# design.net
KiCad netlist of a schematic drawn in Altium Designer
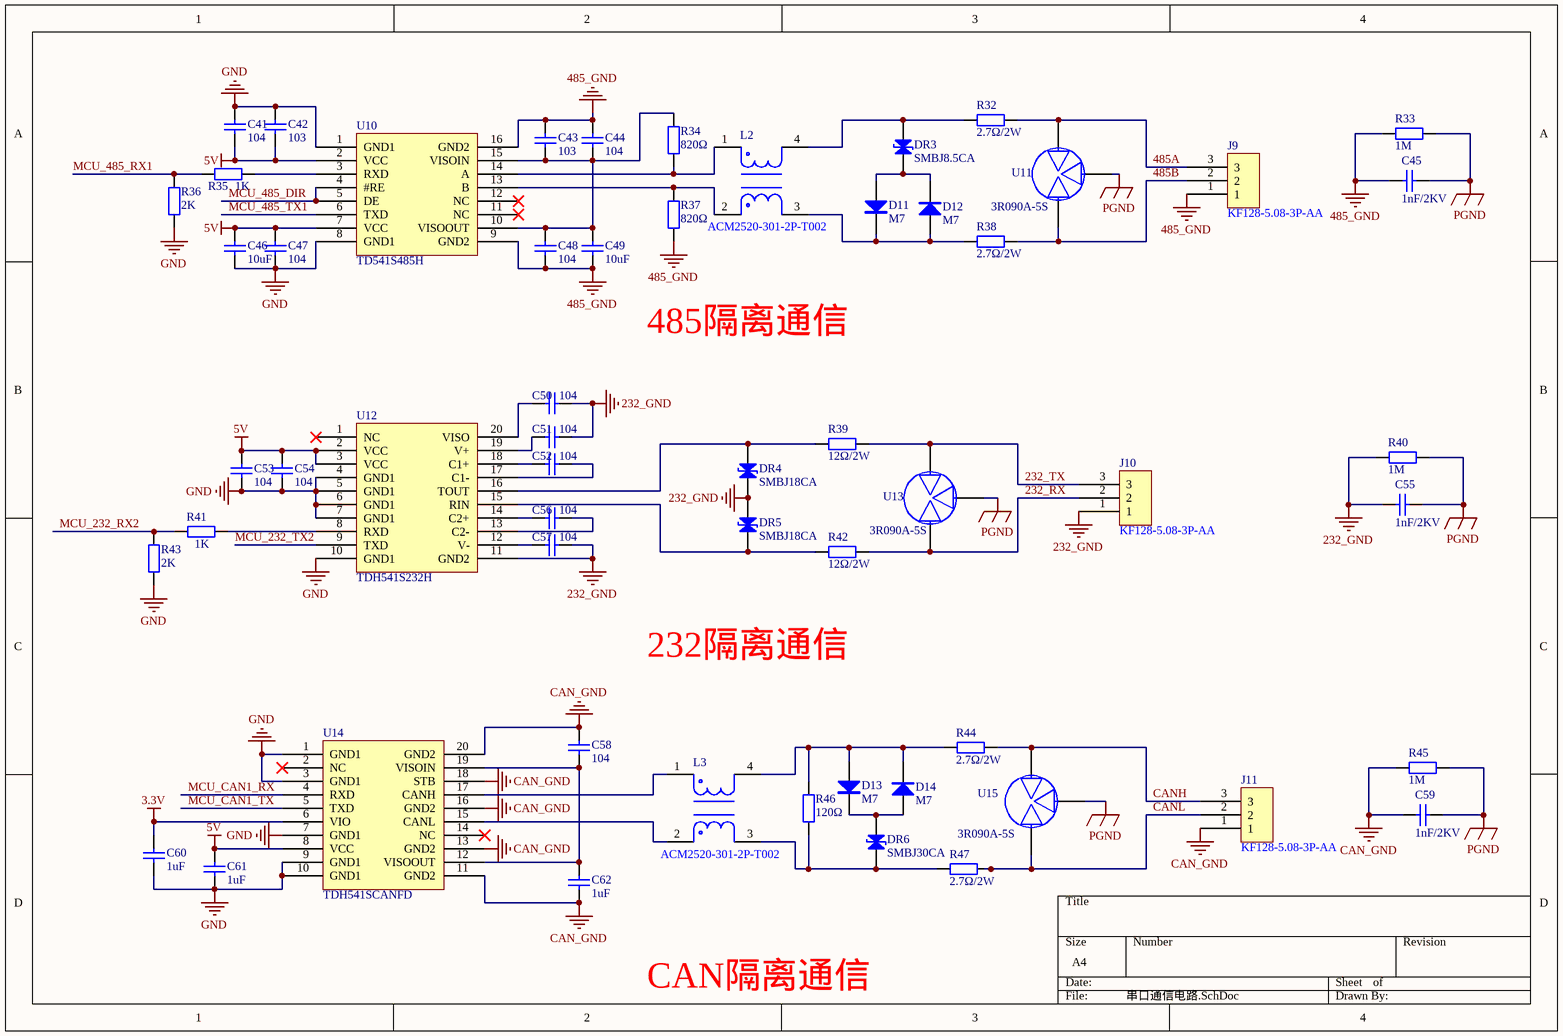
[diagram p0: 串口通信电路.SchDoc]

(export (version "E")
  (design (tool "Eeschema 10.0.6"))
  (components
    (comp (ref "C41")
      (value "104")
      (footprint "C 0603_L")
      (description "0603贴片电容")
      (fields (field (name "PUBLISHER") "Altium Limited"))
      (libsource (lib "STM32_PLC_20251215") (part "Cap"))
    )
    (comp (ref "C42")
      (value "103")
      (footprint "C 0603_L")
      (description "0603贴片电容")
      (fields (field (name "PUBLISHER") "Altium Limited"))
      (libsource (lib "STM32_PLC_20251215") (part "Cap"))
    )
    (comp (ref "C43")
      (value "103")
      (footprint "C 0603_L")
      (description "0603贴片电容")
      (fields (field (name "PUBLISHER") "Altium Limited"))
      (libsource (lib "STM32_PLC_20251215") (part "Cap"))
    )
    (comp (ref "C44")
      (value "104")
      (footprint "C 0603_L")
      (description "0603贴片电容")
      (fields (field (name "PUBLISHER") "Altium Limited"))
      (libsource (lib "STM32_PLC_20251215") (part "Cap"))
    )
    (comp (ref "C45")
      (value "1nF/2KV")
      (footprint "C1206_L")
      (description "0603贴片电容")
      (fields (field (name "PUBLISHER") "Altium Limited"))
      (libsource (lib "STM32_PLC_20251215") (part "Cap"))
    )
    (comp (ref "C46")
      (value "10uF")
      (footprint "C 0603_L")
      (description "0603贴片电容")
      (fields (field (name "PUBLISHER") "Altium Limited"))
      (libsource (lib "STM32_PLC_20251215") (part "Cap"))
    )
    (comp (ref "C47")
      (value "104")
      (footprint "C 0603_L")
      (description "0603贴片电容")
      (fields (field (name "PUBLISHER") "Altium Limited"))
      (libsource (lib "STM32_PLC_20251215") (part "Cap"))
    )
    (comp (ref "C48")
      (value "104")
      (footprint "C 0603_L")
      (description "0603贴片电容")
      (fields (field (name "PUBLISHER") "Altium Limited"))
      (libsource (lib "STM32_PLC_20251215") (part "Cap"))
    )
    (comp (ref "C49")
      (value "10uF")
      (footprint "C 0603_L")
      (description "0603贴片电容")
      (fields (field (name "PUBLISHER") "Altium Limited"))
      (libsource (lib "STM32_PLC_20251215") (part "Cap"))
    )
    (comp (ref "C50")
      (value "104")
      (footprint "C 0603_L")
      (description "0603贴片电容")
      (fields (field (name "PUBLISHER") "Altium Limited"))
      (libsource (lib "STM32_PLC_20251215") (part "Cap"))
    )
    (comp (ref "C51")
      (value "104")
      (footprint "C 0603_L")
      (description "0603贴片电容")
      (fields (field (name "PUBLISHER") "Altium Limited"))
      (libsource (lib "STM32_PLC_20251215") (part "Cap"))
    )
    (comp (ref "C52")
      (value "104")
      (footprint "C 0603_L")
      (description "0603贴片电容")
      (fields (field (name "PUBLISHER") "Altium Limited"))
      (libsource (lib "STM32_PLC_20251215") (part "Cap"))
    )
    (comp (ref "C53")
      (value "104")
      (footprint "C 0603_L")
      (description "0603贴片电容")
      (fields (field (name "PUBLISHER") "Altium Limited"))
      (libsource (lib "STM32_PLC_20251215") (part "Cap"))
    )
    (comp (ref "C54")
      (value "104")
      (footprint "C 0603_L")
      (description "0603贴片电容")
      (fields (field (name "PUBLISHER") "Altium Limited"))
      (libsource (lib "STM32_PLC_20251215") (part "Cap"))
    )
    (comp (ref "C55")
      (value "1nF/2KV")
      (footprint "C1206_L")
      (description "0603贴片电容")
      (fields (field (name "PUBLISHER") "Altium Limited"))
      (libsource (lib "STM32_PLC_20251215") (part "Cap"))
    )
    (comp (ref "C56")
      (value "104")
      (footprint "C 0603_L")
      (description "0603贴片电容")
      (fields (field (name "PUBLISHER") "Altium Limited"))
      (libsource (lib "STM32_PLC_20251215") (part "Cap"))
    )
    (comp (ref "C57")
      (value "104")
      (footprint "C 0603_L")
      (description "0603贴片电容")
      (fields (field (name "PUBLISHER") "Altium Limited"))
      (libsource (lib "STM32_PLC_20251215") (part "Cap"))
    )
    (comp (ref "C58")
      (value "104")
      (footprint "C 0603_L")
      (description "0603贴片电容")
      (fields (field (name "PUBLISHER") "Altium Limited"))
      (libsource (lib "STM32_PLC_20251215") (part "Cap"))
    )
    (comp (ref "C59")
      (value "1nF/2KV")
      (footprint "C1206_L")
      (description "0603贴片电容")
      (fields (field (name "PUBLISHER") "Altium Limited"))
      (libsource (lib "STM32_PLC_20251215") (part "Cap"))
    )
    (comp (ref "C60")
      (value "1uF")
      (footprint "C 0603_L")
      (description "0603贴片电容")
      (fields (field (name "PUBLISHER") "Altium Limited"))
      (libsource (lib "STM32_PLC_20251215") (part "Cap"))
    )
    (comp (ref "C61")
      (value "1uF")
      (footprint "C 0603_L")
      (description "0603贴片电容")
      (fields (field (name "PUBLISHER") "Altium Limited"))
      (libsource (lib "STM32_PLC_20251215") (part "Cap"))
    )
    (comp (ref "C62")
      (value "1uF")
      (footprint "C 0603_L")
      (description "0603贴片电容")
      (fields (field (name "PUBLISHER") "Altium Limited"))
      (libsource (lib "STM32_PLC_20251215") (part "Cap"))
    )
    (comp (ref "D11")
      (value "M7")
      (footprint "SMA")
      (description "整流二极管")
      (libsource (lib "STM32_PLC_20251215_1") (part "M7"))
    )
    (comp (ref "D12")
      (value "M7")
      (footprint "SMA")
      (description "整流二极管")
      (libsource (lib "STM32_PLC_20251215_1") (part "M7"))
    )
    (comp (ref "D13")
      (value "M7")
      (footprint "SMA")
      (description "整流二极管")
      (libsource (lib "STM32_PLC_20251215_1") (part "M7"))
    )
    (comp (ref "D14")
      (value "M7")
      (footprint "SMA")
      (description "整流二极管")
      (libsource (lib "STM32_PLC_20251215_1") (part "M7"))
    )
    (comp (ref "DR3")
      (value "SMBJ8.5CA")
      (footprint "SMB")
      (description "SMB,瞬态抑制二极管")
      (fields (field (name "版权归属") "源创客"))
      (libsource (lib "STM32_PLC_20251215") (part "TVS"))
    )
    (comp (ref "DR4")
      (value "SMBJ18CA")
      (footprint "SMB")
      (description "SMB,瞬态抑制二极管")
      (fields (field (name "版权归属") "源创客"))
      (libsource (lib "STM32_PLC_20251215") (part "TVS"))
    )
    (comp (ref "DR5")
      (value "SMBJ18CA")
      (footprint "SMB")
      (description "SMB,瞬态抑制二极管")
      (fields (field (name "版权归属") "源创客"))
      (libsource (lib "STM32_PLC_20251215") (part "TVS"))
    )
    (comp (ref "DR6")
      (value "SMBJ30CA")
      (footprint "SMB")
      (description "SMB,瞬态抑制二极管")
      (fields (field (name "版权归属") "源创客"))
      (libsource (lib "STM32_PLC_20251215") (part "TVS"))
    )
    (comp (ref "J9")
      (value "KF128-5.08-3P-AA")
      (footprint "KF128-5.08-3P")
      (description "KF128-5.08-3P-AA端座")
      (fields (field (name "MANUFACTURER") "KEFA(科发)"))
      (libsource (lib "STM32_PLC_20251215_1") (part "KF128-5.08-3P-AA"))
    )
    (comp (ref "J10")
      (value "KF128-5.08-3P-AA")
      (footprint "KF128-5.08-3P")
      (description "KF128-5.08-3P-AA端座")
      (fields (field (name "MANUFACTURER") "KEFA(科发)"))
      (libsource (lib "STM32_PLC_20251215_1") (part "KF128-5.08-3P-AA"))
    )
    (comp (ref "J11")
      (value "KF128-5.08-3P-AA")
      (footprint "KF128-5.08-3P")
      (description "KF128-5.08-3P-AA端座")
      (fields (field (name "MANUFACTURER") "KEFA(科发)"))
      (libsource (lib "STM32_PLC_20251215_1") (part "KF128-5.08-3P-AA"))
    )
    (comp (ref "L2")
      (value "ACM2520-301-2P-T002")
      (footprint "FILTER-SMD_4P-L2.5-W2.0-BL")
      (description "共模电感")
      (fields (field (name "MANUFACTURER") "TDK"))
      (libsource (lib "STM32_PLC_20251215_1") (part "ACM2520-301-2P-T002"))
    )
    (comp (ref "L3")
      (value "ACM2520-301-2P-T002")
      (footprint "FILTER-SMD_4P-L2.5-W2.0-BL")
      (description "共模电感")
      (fields (field (name "MANUFACTURER") "TDK"))
      (libsource (lib "STM32_PLC_20251215_1") (part "ACM2520-301-2P-T002"))
    )
    (comp (ref "R32")
      (value "2.7Ω/2W")
      (footprint "R2512_L")
      (description "0603贴片电阻")
      (fields (field (name "版权归属") "源创客"))
      (libsource (lib "STM32_PLC_20251215") (part "Res"))
    )
    (comp (ref "R33")
      (value "1M")
      (footprint "R1206_L")
      (description "0603贴片电阻")
      (fields (field (name "版权归属") "源创客"))
      (libsource (lib "STM32_PLC_20251215") (part "Res"))
    )
    (comp (ref "R34")
      (value "820Ω")
      (footprint "R 0603_L")
      (description "0603贴片电阻")
      (fields (field (name "版权归属") "源创客"))
      (libsource (lib "STM32_PLC_20251215") (part "Res"))
    )
    (comp (ref "R35")
      (value "1K")
      (footprint "R 0603_L")
      (description "0603贴片电阻")
      (fields (field (name "版权归属") "源创客"))
      (libsource (lib "STM32_PLC_20251215") (part "Res"))
    )
    (comp (ref "R36")
      (value "2K")
      (footprint "R 0603_L")
      (description "0603贴片电阻")
      (fields (field (name "版权归属") "源创客"))
      (libsource (lib "STM32_PLC_20251215") (part "Res"))
    )
    (comp (ref "R37")
      (value "820Ω")
      (footprint "R 0603_L")
      (description "0603贴片电阻")
      (fields (field (name "版权归属") "源创客"))
      (libsource (lib "STM32_PLC_20251215") (part "Res"))
    )
    (comp (ref "R38")
      (value "2.7Ω/2W")
      (footprint "R2512_L")
      (description "0603贴片电阻")
      (fields (field (name "版权归属") "源创客"))
      (libsource (lib "STM32_PLC_20251215") (part "Res"))
    )
    (comp (ref "R39")
      (value "12Ω/2W")
      (footprint "R2512_L")
      (description "0603贴片电阻")
      (fields (field (name "版权归属") "源创客"))
      (libsource (lib "STM32_PLC_20251215") (part "Res"))
    )
    (comp (ref "R40")
      (value "1M")
      (footprint "R1206_L")
      (description "0603贴片电阻")
      (fields (field (name "版权归属") "源创客"))
      (libsource (lib "STM32_PLC_20251215") (part "Res"))
    )
    (comp (ref "R41")
      (value "1K")
      (footprint "R 0603_L")
      (description "0603贴片电阻")
      (fields (field (name "版权归属") "源创客"))
      (libsource (lib "STM32_PLC_20251215") (part "Res"))
    )
    (comp (ref "R42")
      (value "12Ω/2W")
      (footprint "R2512_L")
      (description "0603贴片电阻")
      (fields (field (name "版权归属") "源创客"))
      (libsource (lib "STM32_PLC_20251215") (part "Res"))
    )
    (comp (ref "R43")
      (value "2K")
      (footprint "R 0603_L")
      (description "0603贴片电阻")
      (fields (field (name "版权归属") "源创客"))
      (libsource (lib "STM32_PLC_20251215") (part "Res"))
    )
    (comp (ref "R44")
      (value "2.7Ω/2W")
      (footprint "R2512_L")
      (description "0603贴片电阻")
      (fields (field (name "版权归属") "源创客"))
      (libsource (lib "STM32_PLC_20251215") (part "Res"))
    )
    (comp (ref "R45")
      (value "1M")
      (footprint "R1206_L")
      (description "0603贴片电阻")
      (fields (field (name "版权归属") "源创客"))
      (libsource (lib "STM32_PLC_20251215") (part "Res"))
    )
    (comp (ref "R46")
      (value "120Ω")
      (footprint "R 0603_L")
      (description "0603贴片电阻")
      (fields (field (name "版权归属") "源创客"))
      (libsource (lib "STM32_PLC_20251215") (part "Res"))
    )
    (comp (ref "R47")
      (value "2.7Ω/2W")
      (footprint "R2512_L")
      (description "0603贴片电阻")
      (fields (field (name "版权归属") "源创客"))
      (libsource (lib "STM32_PLC_20251215") (part "Res"))
    )
    (comp (ref "U10")
      (value "TD541S485H")
      (footprint "DFN-16_L13.0-W10.0-P1.27-BL")
      (description "金升阳485隔离芯片（带隔离电源）")
      (fields (field (name "MANUFACTURER") "MORNSUN(金升阳)"))
      (libsource (lib "STM32F407_PLC_20260104_") (part "TD541S485H"))
    )
    (comp (ref "U11")
      (value "3R090A-5S")
      (footprint "DIO-DT-SMD_L7.5-W5.0")
      (description "气体放电管")
      (fields (field (name "MANUFACTURER") "R+O(宏嘉诚)") (field (name "TOLERANCE") "±20%"))
      (libsource (lib "STM32F407_PLC_20260104_") (part "3R090A-5S_C48642393"))
    )
    (comp (ref "U12")
      (value "TDH541S232H")
      (footprint "DFN-20_L13.0-W10.0-P1.27-BL")
      (description "金升阳232隔离芯片（带隔离电源）")
      (fields (field (name "MANUFACTURER") "MORNSUN(金升阳)"))
      (libsource (lib "STM32F407_PLC_20260104_") (part "TDH541S232H"))
    )
    (comp (ref "U13")
      (value "3R090A-5S")
      (footprint "DIO-DT-SMD_L7.5-W5.0")
      (description "气体放电管")
      (fields (field (name "MANUFACTURER") "R+O(宏嘉诚)") (field (name "TOLERANCE") "±20%"))
      (libsource (lib "STM32F407_PLC_20260104_") (part "3R090A-5S_C48642393"))
    )
    (comp (ref "U14")
      (value "TDH541SCANFD")
      (footprint "DFN-20_L13.0-W10.0-P1.27-BL")
      (description "金升阳CAN芯片（带隔离电源）")
      (fields (field (name "MANUFACTURER") "MORNSUN(金升阳)"))
      (libsource (lib "STM32F407_PLC_20260104_") (part "TDH541SCANFD"))
    )
    (comp (ref "U15")
      (value "3R090A-5S")
      (footprint "DIO-DT-SMD_L7.5-W5.0")
      (description "气体放电管")
      (fields (field (name "MANUFACTURER") "R+O(宏嘉诚)") (field (name "TOLERANCE") "±20%"))
      (libsource (lib "STM32F407_PLC_20260104_") (part "3R090A-5S_C48642393"))
    )
  )
  (nets
    (net (code "1") (name "/232_RX") (class "Default")
      (node (ref "J10") (pin "2") (pinfunction "2_2") (pintype "passive"))
      (node (ref "R42") (pin "2") (pinfunction "2_2") (pintype "passive"))
      (node (ref "U13") (pin "3") (pinfunction "3_3") (pintype "passive"))
    )
    (net (code "2") (name "/232_TX") (class "Default")
      (node (ref "J10") (pin "3") (pinfunction "3_3") (pintype "passive"))
      (node (ref "R39") (pin "2") (pinfunction "2_2") (pintype "passive"))
      (node (ref "U13") (pin "1") (pinfunction "1_1") (pintype "passive"))
    )
    (net (code "3") (name "/485A") (class "Default")
      (node (ref "J9") (pin "3") (pinfunction "3_3") (pintype "passive"))
      (node (ref "R32") (pin "2") (pinfunction "2_2") (pintype "passive"))
      (node (ref "U11") (pin "1") (pinfunction "1_1") (pintype "passive"))
    )
    (net (code "4") (name "/485B") (class "Default")
      (node (ref "J9") (pin "2") (pinfunction "2_2") (pintype "passive"))
      (node (ref "R38") (pin "2") (pinfunction "2_2") (pintype "passive"))
      (node (ref "U11") (pin "3") (pinfunction "3_3") (pintype "passive"))
    )
    (net (code "5") (name "/CANH") (class "Default")
      (node (ref "J11") (pin "3") (pinfunction "3_3") (pintype "passive"))
      (node (ref "R44") (pin "2") (pinfunction "2_2") (pintype "passive"))
      (node (ref "U15") (pin "1") (pinfunction "1_1") (pintype "passive"))
    )
    (net (code "6") (name "/CANL") (class "Default")
      (node (ref "J11") (pin "2") (pinfunction "2_2") (pintype "passive"))
      (node (ref "R47") (pin "2") (pinfunction "2_2") (pintype "passive"))
      (node (ref "U15") (pin "3") (pinfunction "3_3") (pintype "passive"))
    )
    (net (code "7") (name "/MCU_232_RX2") (class "Default")
      (node (ref "R41") (pin "2") (pinfunction "2_2") (pintype "passive"))
      (node (ref "R43") (pin "2") (pinfunction "2_2") (pintype "passive"))
    )
    (net (code "8") (name "/MCU_232_TX2") (class "Default")
      (node (ref "U12") (pin "9") (pinfunction "TXD_9") (pintype "passive"))
    )
    (net (code "9") (name "/MCU_485_DIR") (class "Default")
      (node (ref "U10") (pin "4") (pinfunction "#RE_4") (pintype "passive"))
      (node (ref "U10") (pin "5") (pinfunction "DE_5") (pintype "passive"))
    )
    (net (code "10") (name "/MCU_485_RX1") (class "Default")
      (node (ref "R35") (pin "1") (pinfunction "1_1") (pintype "passive"))
      (node (ref "R36") (pin "2") (pinfunction "2_2") (pintype "passive"))
    )
    (net (code "11") (name "/MCU_485_TX1") (class "Default")
      (node (ref "U10") (pin "6") (pinfunction "TXD_6") (pintype "passive"))
    )
    (net (code "12") (name "/MCU_CAN1_RX") (class "Default")
      (node (ref "U14") (pin "4") (pinfunction "RXD_4") (pintype "passive"))
    )
    (net (code "13") (name "/MCU_CAN1_TX") (class "Default")
      (node (ref "U14") (pin "5") (pinfunction "TXD_5") (pintype "passive"))
    )
    (net (code "14") (name "3.3V") (class "Default")
      (node (ref "C60") (pin "2") (pinfunction "2_2") (pintype "passive"))
      (node (ref "U14") (pin "6") (pinfunction "VIO_6") (pintype "passive"))
    )
    (net (code "15") (name "5V") (class "Default")
      (node (ref "C41") (pin "1") (pinfunction "1_1") (pintype "passive"))
      (node (ref "C42") (pin "1") (pinfunction "1_1") (pintype "passive"))
      (node (ref "C46") (pin "2") (pinfunction "2_2") (pintype "passive"))
      (node (ref "C47") (pin "2") (pinfunction "2_2") (pintype "passive"))
      (node (ref "C53") (pin "2") (pinfunction "2_2") (pintype "passive"))
      (node (ref "C54") (pin "2") (pinfunction "2_2") (pintype "passive"))
      (node (ref "C61") (pin "2") (pinfunction "2_2") (pintype "passive"))
      (node (ref "U10") (pin "2") (pinfunction "VCC_2") (pintype "passive"))
      (node (ref "U10") (pin "7") (pinfunction "VCC_7") (pintype "passive"))
      (node (ref "U12") (pin "2") (pinfunction "VCC_2") (pintype "passive"))
      (node (ref "U12") (pin "3") (pinfunction "VCC_3") (pintype "passive"))
      (node (ref "U14") (pin "8") (pinfunction "VCC_8") (pintype "passive"))
    )
    (net (code "16") (name "232_GND") (class "Default")
      (node (ref "C50") (pin "1") (pinfunction "1_1") (pintype "passive"))
      (node (ref "C51") (pin "1") (pinfunction "1_1") (pintype "passive"))
      (node (ref "C55") (pin "1") (pinfunction "1_1") (pintype "passive"))
      (node (ref "C57") (pin "1") (pinfunction "1_1") (pintype "passive"))
      (node (ref "DR4") (pin "2") (pinfunction "K_2") (pintype "passive"))
      (node (ref "DR5") (pin "1") (pinfunction "A_1") (pintype "passive"))
      (node (ref "J10") (pin "1") (pinfunction "1_1") (pintype "passive"))
      (node (ref "R40") (pin "1") (pinfunction "1_1") (pintype "passive"))
      (node (ref "U12") (pin "11") (pinfunction "GND2_11") (pintype "passive"))
    )
    (net (code "17") (name "485_GND") (class "Default")
      (node (ref "C43") (pin "2") (pinfunction "2_2") (pintype "passive"))
      (node (ref "C44") (pin "2") (pinfunction "2_2") (pintype "passive"))
      (node (ref "C45") (pin "1") (pinfunction "1_1") (pintype "passive"))
      (node (ref "C48") (pin "1") (pinfunction "1_1") (pintype "passive"))
      (node (ref "C49") (pin "1") (pinfunction "1_1") (pintype "passive"))
      (node (ref "J9") (pin "1") (pinfunction "1_1") (pintype "passive"))
      (node (ref "R33") (pin "1") (pinfunction "1_1") (pintype "passive"))
      (node (ref "R37") (pin "1") (pinfunction "1_1") (pintype "passive"))
      (node (ref "U10") (pin "16") (pinfunction "GND2_16") (pintype "passive"))
      (node (ref "U10") (pin "9") (pinfunction "GND2_9") (pintype "passive"))
    )
    (net (code "18") (name "CAN_GND") (class "Default")
      (node (ref "C58") (pin "2") (pinfunction "2_2") (pintype "passive"))
      (node (ref "C59") (pin "1") (pinfunction "1_1") (pintype "passive"))
      (node (ref "C62") (pin "1") (pinfunction "1_1") (pintype "passive"))
      (node (ref "J11") (pin "1") (pinfunction "1_1") (pintype "passive"))
      (node (ref "R45") (pin "1") (pinfunction "1_1") (pintype "passive"))
      (node (ref "U14") (pin "11") (pinfunction "GND2_11") (pintype "passive"))
      (node (ref "U14") (pin "13") (pinfunction "GND2_13") (pintype "passive"))
      (node (ref "U14") (pin "16") (pinfunction "GND2_16") (pintype "passive"))
      (node (ref "U14") (pin "18") (pinfunction "STB_18") (pintype "passive"))
      (node (ref "U14") (pin "20") (pinfunction "GND2_20") (pintype "passive"))
    )
    (net (code "19") (name "GND") (class "Default")
      (node (ref "C41") (pin "2") (pinfunction "2_2") (pintype "passive"))
      (node (ref "C42") (pin "2") (pinfunction "2_2") (pintype "passive"))
      (node (ref "C46") (pin "1") (pinfunction "1_1") (pintype "passive"))
      (node (ref "C47") (pin "1") (pinfunction "1_1") (pintype "passive"))
      (node (ref "C53") (pin "1") (pinfunction "1_1") (pintype "passive"))
      (node (ref "C54") (pin "1") (pinfunction "1_1") (pintype "passive"))
      (node (ref "C60") (pin "1") (pinfunction "1_1") (pintype "passive"))
      (node (ref "C61") (pin "1") (pinfunction "1_1") (pintype "passive"))
      (node (ref "R36") (pin "1") (pinfunction "1_1") (pintype "passive"))
      (node (ref "R43") (pin "1") (pinfunction "1_1") (pintype "passive"))
      (node (ref "U10") (pin "1") (pinfunction "GND1_1") (pintype "passive"))
      (node (ref "U10") (pin "8") (pinfunction "GND1_8") (pintype "passive"))
      (node (ref "U12") (pin "10") (pinfunction "GND1_10") (pintype "passive"))
      (node (ref "U12") (pin "4") (pinfunction "GND1_4") (pintype "passive"))
      (node (ref "U12") (pin "5") (pinfunction "GND1_5") (pintype "passive"))
      (node (ref "U12") (pin "6") (pinfunction "GND1_6") (pintype "passive"))
      (node (ref "U12") (pin "7") (pinfunction "GND1_7") (pintype "passive"))
      (node (ref "U14") (pin "1") (pinfunction "GND1_1") (pintype "passive"))
      (node (ref "U14") (pin "10") (pinfunction "GND1_10") (pintype "passive"))
      (node (ref "U14") (pin "3") (pinfunction "GND1_3") (pintype "passive"))
      (node (ref "U14") (pin "7") (pinfunction "GND1_7") (pintype "passive"))
      (node (ref "U14") (pin "9") (pinfunction "GND1_9") (pintype "passive"))
    )
    (net (code "20") (name "Net-(D11-A)") (class "Default")
      (node (ref "D11") (pin "1") (pinfunction "A_1") (pintype "passive"))
      (node (ref "D12") (pin "2") (pinfunction "K_2") (pintype "passive"))
      (node (ref "DR3") (pin "2") (pinfunction "K_2") (pintype "passive"))
    )
    (net (code "21") (name "Net-(D11-K)") (class "Default")
      (node (ref "D11") (pin "2") (pinfunction "K_2") (pintype "passive"))
      (node (ref "D12") (pin "1") (pinfunction "A_1") (pintype "passive"))
      (node (ref "L2") (pin "3") (pinfunction "3_3") (pintype "passive"))
      (node (ref "R38") (pin "1") (pinfunction "1_1") (pintype "passive"))
    )
    (net (code "22") (name "Net-(D13-A)") (class "Default")
      (node (ref "D13") (pin "1") (pinfunction "A_1") (pintype "passive"))
      (node (ref "D14") (pin "2") (pinfunction "K_2") (pintype "passive"))
      (node (ref "L3") (pin "4") (pinfunction "4_4") (pintype "passive"))
      (node (ref "R44") (pin "1") (pinfunction "1_1") (pintype "passive"))
      (node (ref "R46") (pin "1") (pinfunction "1_1") (pintype "passive"))
    )
    (net (code "23") (name "Net-(D13-K)") (class "Default")
      (node (ref "D13") (pin "2") (pinfunction "K_2") (pintype "passive"))
      (node (ref "D14") (pin "1") (pinfunction "A_1") (pintype "passive"))
      (node (ref "DR6") (pin "2") (pinfunction "K_2") (pintype "passive"))
    )
    (net (code "24") (name "Net-(DR3-A)") (class "Default")
      (node (ref "DR3") (pin "1") (pinfunction "A_1") (pintype "passive"))
      (node (ref "L2") (pin "4") (pinfunction "4_4") (pintype "passive"))
      (node (ref "R32") (pin "1") (pinfunction "1_1") (pintype "passive"))
    )
    (net (code "25") (name "Net-(DR4-A)") (class "Default")
      (node (ref "DR4") (pin "1") (pinfunction "A_1") (pintype "passive"))
      (node (ref "R39") (pin "1") (pinfunction "1_1") (pintype "passive"))
      (node (ref "U12") (pin "16") (pinfunction "TOUT_16") (pintype "passive"))
    )
    (net (code "26") (name "Net-(DR5-K)") (class "Default")
      (node (ref "DR5") (pin "2") (pinfunction "K_2") (pintype "passive"))
      (node (ref "R42") (pin "1") (pinfunction "1_1") (pintype "passive"))
      (node (ref "U12") (pin "15") (pinfunction "RIN_15") (pintype "passive"))
    )
    (net (code "27") (name "Net-(DR6-A)") (class "Default")
      (node (ref "DR6") (pin "1") (pinfunction "A_1") (pintype "passive"))
      (node (ref "L3") (pin "3") (pinfunction "3_3") (pintype "passive"))
      (node (ref "R46") (pin "2") (pinfunction "2_2") (pintype "passive"))
      (node (ref "R47") (pin "1") (pinfunction "1_1") (pintype "passive"))
    )
    (net (code "28") (name "Net-(U10-A)") (class "Default")
      (node (ref "L2") (pin "1") (pinfunction "1_1") (pintype "passive"))
      (node (ref "R34") (pin "1") (pinfunction "1_1") (pintype "passive"))
      (node (ref "U10") (pin "14") (pinfunction "A_14") (pintype "passive"))
    )
    (net (code "29") (name "Net-(U10-B)") (class "Default")
      (node (ref "L2") (pin "2") (pinfunction "2_2") (pintype "passive"))
      (node (ref "R37") (pin "2") (pinfunction "2_2") (pintype "passive"))
      (node (ref "U10") (pin "13") (pinfunction "B_13") (pintype "passive"))
    )
    (net (code "30") (name "Net-(U10-RXD)") (class "Default")
      (node (ref "R35") (pin "2") (pinfunction "2_2") (pintype "passive"))
      (node (ref "U10") (pin "3") (pinfunction "RXD_3") (pintype "passive"))
    )
    (net (code "31") (name "Net-(U10-VISOIN)") (class "Default")
      (node (ref "C43") (pin "1") (pinfunction "1_1") (pintype "passive"))
      (node (ref "C44") (pin "1") (pinfunction "1_1") (pintype "passive"))
      (node (ref "C48") (pin "2") (pinfunction "2_2") (pintype "passive"))
      (node (ref "C49") (pin "2") (pinfunction "2_2") (pintype "passive"))
      (node (ref "R34") (pin "2") (pinfunction "2_2") (pintype "passive"))
      (node (ref "U10") (pin "10") (pinfunction "VISOOUT_10") (pintype "passive"))
      (node (ref "U10") (pin "15") (pinfunction "VISOIN_15") (pintype "passive"))
    )
    (net (code "32") (name "Net-(U12-C1+)") (class "Default")
      (node (ref "C52") (pin "2") (pinfunction "2_2") (pintype "passive"))
      (node (ref "U12") (pin "18") (pinfunction "C1+_18") (pintype "passive"))
    )
    (net (code "33") (name "Net-(U12-C1-)") (class "Default")
      (node (ref "C52") (pin "1") (pinfunction "1_1") (pintype "passive"))
      (node (ref "U12") (pin "17") (pinfunction "C1-_17") (pintype "passive"))
    )
    (net (code "34") (name "Net-(U12-C2+)") (class "Default")
      (node (ref "C56") (pin "2") (pinfunction "2_2") (pintype "passive"))
      (node (ref "U12") (pin "14") (pinfunction "C2+_14") (pintype "passive"))
    )
    (net (code "35") (name "Net-(U12-C2-)") (class "Default")
      (node (ref "C56") (pin "1") (pinfunction "1_1") (pintype "passive"))
      (node (ref "U12") (pin "13") (pinfunction "C2-_13") (pintype "passive"))
    )
    (net (code "36") (name "Net-(U12-RXD)") (class "Default")
      (node (ref "R41") (pin "1") (pinfunction "1_1") (pintype "passive"))
      (node (ref "U12") (pin "8") (pinfunction "RXD_8") (pintype "passive"))
    )
    (net (code "37") (name "Net-(U12-V+)") (class "Default")
      (node (ref "C51") (pin "2") (pinfunction "2_2") (pintype "passive"))
      (node (ref "U12") (pin "19") (pinfunction "V+_19") (pintype "passive"))
    )
    (net (code "38") (name "Net-(U12-V-)") (class "Default")
      (node (ref "C57") (pin "2") (pinfunction "2_2") (pintype "passive"))
      (node (ref "U12") (pin "12") (pinfunction "V-_12") (pintype "passive"))
    )
    (net (code "39") (name "Net-(U12-VISO)") (class "Default")
      (node (ref "C50") (pin "2") (pinfunction "2_2") (pintype "passive"))
      (node (ref "U12") (pin "20") (pinfunction "VISO_20") (pintype "passive"))
    )
    (net (code "40") (name "Net-(U14-CANH)") (class "Default")
      (node (ref "L3") (pin "1") (pinfunction "1_1") (pintype "passive"))
      (node (ref "U14") (pin "17") (pinfunction "CANH_17") (pintype "passive"))
    )
    (net (code "41") (name "Net-(U14-CANL)") (class "Default")
      (node (ref "L3") (pin "2") (pinfunction "2_2") (pintype "passive"))
      (node (ref "U14") (pin "15") (pinfunction "CANL_15") (pintype "passive"))
    )
    (net (code "42") (name "Net-(U14-VISOIN)") (class "Default")
      (node (ref "C58") (pin "1") (pinfunction "1_1") (pintype "passive"))
      (node (ref "C62") (pin "2") (pinfunction "2_2") (pintype "passive"))
      (node (ref "U14") (pin "12") (pinfunction "VISOOUT_12") (pintype "passive"))
      (node (ref "U14") (pin "19") (pinfunction "VISOIN_19") (pintype "passive"))
    )
    (net (code "43") (name "PGND") (class "Default")
      (node (ref "C45") (pin "2") (pinfunction "2_2") (pintype "passive"))
      (node (ref "C55") (pin "2") (pinfunction "2_2") (pintype "passive"))
      (node (ref "C59") (pin "2") (pinfunction "2_2") (pintype "passive"))
      (node (ref "R33") (pin "2") (pinfunction "2_2") (pintype "passive"))
      (node (ref "R40") (pin "2") (pinfunction "2_2") (pintype "passive"))
      (node (ref "R45") (pin "2") (pinfunction "2_2") (pintype "passive"))
      (node (ref "U11") (pin "2") (pinfunction "2_2") (pintype "passive"))
      (node (ref "U13") (pin "2") (pinfunction "2_2") (pintype "passive"))
      (node (ref "U15") (pin "2") (pinfunction "2_2") (pintype "passive"))
    )
    (net (code "44") (name "unconnected-(U10-NC-Pad11)") (class "Default")
      (node (ref "U10") (pin "11") (pinfunction "NC_11") (pintype "passive+no_connect"))
    )
    (net (code "45") (name "unconnected-(U10-NC-Pad12)") (class "Default")
      (node (ref "U10") (pin "12") (pinfunction "NC_12") (pintype "passive+no_connect"))
    )
    (net (code "46") (name "unconnected-(U12-NC-Pad1)") (class "Default")
      (node (ref "U12") (pin "1") (pinfunction "NC_1") (pintype "passive+no_connect"))
    )
    (net (code "47") (name "unconnected-(U14-NC-Pad2)") (class "Default")
      (node (ref "U14") (pin "2") (pinfunction "NC_2") (pintype "passive+no_connect"))
    )
    (net (code "48") (name "unconnected-(U14-NC-Pad14)") (class "Default")
      (node (ref "U14") (pin "14") (pinfunction "NC_14") (pintype "passive+no_connect"))
    )
  )
)
